# Photon_Pixel_Shield_v7_no_diode_no_fuse.net
KiCad netlist of a schematic drawn in EAGLE
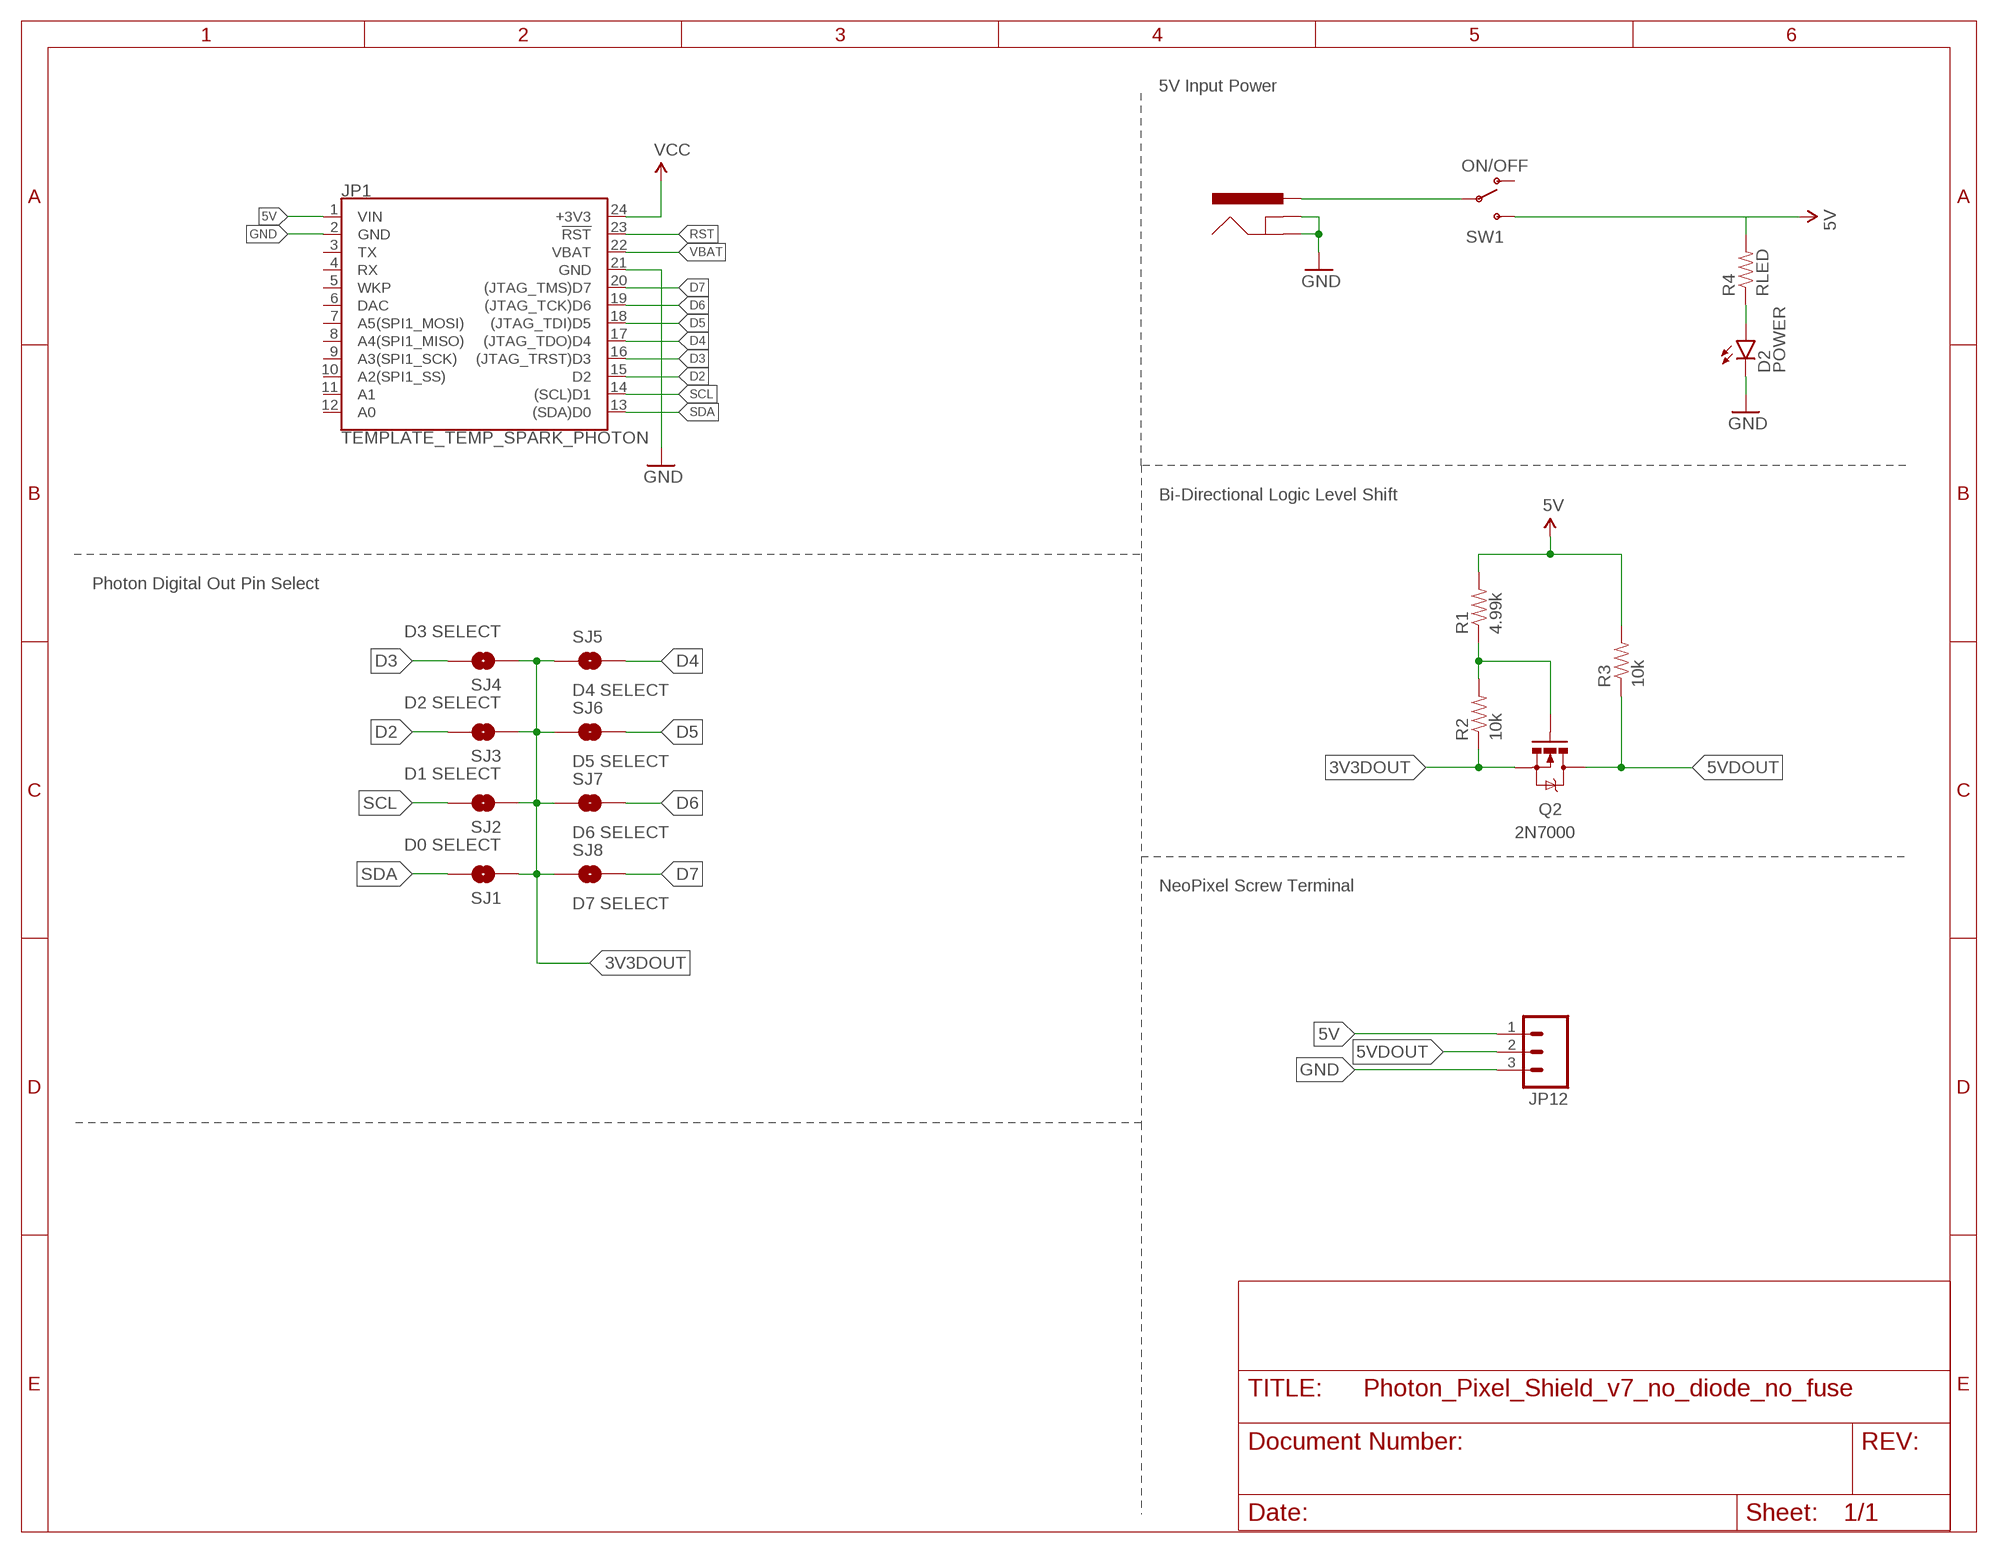
[diagram p0: schematic, sheet 1]

(export (version "E")
  (design (tool "Eeschema 10.0.6"))
  (components
    (comp (ref "D2")
      (value "POWER")
      (footprint "eagle-import:LED3MM")
      (libsource (lib "eagle-import") (part "LED3MM"))
    )
    (comp (ref "J1")
      (value "POWER_JACKPTH")
      (footprint "eagle-import:POWER_JACK_PTH")
      (libsource (lib "eagle-import") (part "POWER_JACKPTH"))
    )
    (comp (ref "JP1")
      (value "TEMPLATE_TEMP_SPARK_PHOTON")
      (footprint "eagle-import:TEMPLATE_TEMP_SPARK_PHOTON")
      (libsource (lib "eagle-import") (part "TEMPLATE_TEMP_SPARK_PHOTON"))
    )
    (comp (ref "JP12")
      (value "M03SCREW")
      (footprint "eagle-import:SCREWTERMINAL-3.5MM-3")
      (libsource (lib "eagle-import") (part "M03SCREW"))
    )
    (comp (ref "Q2")
      (value "2N7000")
      (footprint "eagle-import:TO-92")
      (libsource (lib "eagle-import") (part "MOSFET-NCHANNEL2N7000"))
    )
    (comp (ref "R1")
      (value "4.99k")
      (footprint "eagle-import:AXIAL-0.3")
      (libsource (lib "eagle-import") (part "10KOHM-1/4W-1%(PTH)HORIZ"))
    )
    (comp (ref "R2")
      (value "10k")
      (footprint "eagle-import:AXIAL-0.3")
      (libsource (lib "eagle-import") (part "10KOHM-1/4W-1%(PTH)HORIZ"))
    )
    (comp (ref "R3")
      (value "10k")
      (footprint "eagle-import:AXIAL-0.3")
      (libsource (lib "eagle-import") (part "10KOHM-1/4W-1%(PTH)HORIZ"))
    )
    (comp (ref "R4")
      (value "RLED")
      (footprint "eagle-import:AXIAL-0.3")
      (libsource (lib "eagle-import") (part "10KOHM-1/4W-1%(PTH)HORIZ"))
    )
    (comp (ref "SJ1")
      (value "D0 SELECT")
      (footprint "eagle-import:SJ_2S-NO")
      (libsource (lib "eagle-import") (part "SOLDERJUMPERNO"))
    )
    (comp (ref "SJ2")
      (value "D1 SELECT")
      (footprint "eagle-import:SJ_2S-NO")
      (libsource (lib "eagle-import") (part "SOLDERJUMPERNO"))
    )
    (comp (ref "SJ3")
      (value "D2 SELECT")
      (footprint "eagle-import:SJ_2S-NO")
      (libsource (lib "eagle-import") (part "SOLDERJUMPERNO"))
    )
    (comp (ref "SJ4")
      (value "D3 SELECT")
      (footprint "eagle-import:SJ_2S-NO")
      (libsource (lib "eagle-import") (part "SOLDERJUMPERNO"))
    )
    (comp (ref "SJ5")
      (value "D4 SELECT")
      (footprint "eagle-import:SJ_2S-NO")
      (libsource (lib "eagle-import") (part "SOLDERJUMPERNO"))
    )
    (comp (ref "SJ6")
      (value "D5 SELECT")
      (footprint "eagle-import:SJ_2S-NO")
      (libsource (lib "eagle-import") (part "SOLDERJUMPERNO"))
    )
    (comp (ref "SJ7")
      (value "D6 SELECT")
      (footprint "eagle-import:SJ_2S-NO")
      (libsource (lib "eagle-import") (part "SOLDERJUMPERNO"))
    )
    (comp (ref "SJ8")
      (value "D7 SELECT")
      (footprint "eagle-import:SJ_2S-NO")
      (libsource (lib "eagle-import") (part "SOLDERJUMPERNO"))
    )
    (comp (ref "SW1")
      (value "ON/OFF")
      (footprint "eagle-import:SWITCH-SPST")
      (libsource (lib "eagle-import") (part "SWITCH-SPSTPTH"))
    )
  )
  (nets
    (net (code "1") (name "3V3DOUT") (class "Default")
      (node (ref "Q2") (pin "1") (pinfunction "S_1") (pintype "passive"))
      (node (ref "R2") (pin "P$1") (pinfunction "1_P$1") (pintype "passive"))
      (node (ref "SJ1") (pin "1") (pinfunction "1_1") (pintype "passive"))
      (node (ref "SJ2") (pin "1") (pinfunction "1_1") (pintype "passive"))
      (node (ref "SJ3") (pin "1") (pinfunction "1_1") (pintype "passive"))
      (node (ref "SJ4") (pin "1") (pinfunction "1_1") (pintype "passive"))
      (node (ref "SJ5") (pin "1") (pinfunction "1_1") (pintype "passive"))
      (node (ref "SJ6") (pin "1") (pinfunction "1_1") (pintype "passive"))
      (node (ref "SJ7") (pin "1") (pinfunction "1_1") (pintype "passive"))
      (node (ref "SJ8") (pin "1") (pinfunction "1_1") (pintype "passive"))
    )
    (net (code "2") (name "5V") (class "Default")
      (node (ref "JP1") (pin "1") (pinfunction "VIN_1") (pintype "bidirectional"))
      (node (ref "JP12") (pin "1") (pinfunction "1_1") (pintype "passive"))
      (node (ref "R1") (pin "P$2") (pinfunction "2_P$2") (pintype "passive"))
      (node (ref "R3") (pin "P$2") (pinfunction "2_P$2") (pintype "passive"))
      (node (ref "R4") (pin "P$2") (pinfunction "2_P$2") (pintype "passive"))
      (node (ref "SW1") (pin "3") (pinfunction "S_3") (pintype "passive"))
    )
    (net (code "3") (name "5VDOUT") (class "Default")
      (node (ref "JP12") (pin "2") (pinfunction "2_2") (pintype "passive"))
      (node (ref "Q2") (pin "3") (pinfunction "D_3") (pintype "passive"))
      (node (ref "R3") (pin "P$1") (pinfunction "1_P$1") (pintype "passive"))
    )
    (net (code "4") (name "D2") (class "Default")
      (node (ref "JP1") (pin "15") (pinfunction "D2_15") (pintype "bidirectional"))
      (node (ref "SJ3") (pin "2") (pinfunction "2_2") (pintype "passive"))
    )
    (net (code "5") (name "D3") (class "Default")
      (node (ref "JP1") (pin "16") (pinfunction "(JTAG_TRST)D3_16") (pintype "bidirectional"))
      (node (ref "SJ4") (pin "2") (pinfunction "2_2") (pintype "passive"))
    )
    (net (code "6") (name "D4") (class "Default")
      (node (ref "JP1") (pin "17") (pinfunction "(JTAG_TDO)D4_17") (pintype "bidirectional"))
      (node (ref "SJ5") (pin "2") (pinfunction "2_2") (pintype "passive"))
    )
    (net (code "7") (name "D5") (class "Default")
      (node (ref "JP1") (pin "18") (pinfunction "(JTAG_TDI)D5_18") (pintype "bidirectional"))
      (node (ref "SJ6") (pin "2") (pinfunction "2_2") (pintype "passive"))
    )
    (net (code "8") (name "D6") (class "Default")
      (node (ref "JP1") (pin "19") (pinfunction "(JTAG_TCK)D6_19") (pintype "bidirectional"))
      (node (ref "SJ7") (pin "2") (pinfunction "2_2") (pintype "passive"))
    )
    (net (code "9") (name "D7") (class "Default")
      (node (ref "JP1") (pin "20") (pinfunction "(JTAG_TMS)D7_20") (pintype "bidirectional"))
      (node (ref "SJ8") (pin "2") (pinfunction "2_2") (pintype "passive"))
    )
    (net (code "10") (name "GND") (class "Default")
      (node (ref "D2") (pin "K") (pinfunction "C_K") (pintype "passive"))
      (node (ref "J1") (pin "GND") (pinfunction "GND_GND") (pintype "bidirectional"))
      (node (ref "J1") (pin "GNDBREAK") (pinfunction "GNDBREAK_GNDBREAK") (pintype "bidirectional"))
      (node (ref "JP1") (pin "2") (pinfunction "GND_2") (pintype "bidirectional"))
      (node (ref "JP1") (pin "21") (pinfunction "GND_21") (pintype "bidirectional"))
      (node (ref "JP12") (pin "3") (pinfunction "3_3") (pintype "passive"))
    )
    (net (code "11") (name "Net-(Q2-G)") (class "Default")
      (node (ref "Q2") (pin "2") (pinfunction "G_2") (pintype "passive"))
      (node (ref "R1") (pin "P$1") (pinfunction "1_P$1") (pintype "passive"))
      (node (ref "R2") (pin "P$2") (pinfunction "2_P$2") (pintype "passive"))
    )
    (net (code "12") (name "Net-(R4-1)") (class "Default")
      (node (ref "D2") (pin "A") (pinfunction "A_A") (pintype "passive"))
      (node (ref "R4") (pin "P$1") (pinfunction "1_P$1") (pintype "passive"))
    )
    (net (code "13") (name "Net-(SW1-P)") (class "Default")
      (node (ref "J1") (pin "PWR") (pinfunction "PWR_PWR") (pintype "bidirectional"))
      (node (ref "SW1") (pin "2") (pinfunction "P_2") (pintype "passive"))
    )
    (net (code "14") (name "RST") (class "Default")
      (node (ref "JP1") (pin "23") (pinfunction "~{RST}_23") (pintype "bidirectional"))
    )
    (net (code "15") (name "SCL") (class "Default")
      (node (ref "JP1") (pin "14") (pinfunction "(SCL)D1_14") (pintype "bidirectional"))
      (node (ref "SJ2") (pin "2") (pinfunction "2_2") (pintype "passive"))
    )
    (net (code "16") (name "SDA") (class "Default")
      (node (ref "JP1") (pin "13") (pinfunction "(SDA)D0_13") (pintype "bidirectional"))
      (node (ref "SJ1") (pin "2") (pinfunction "2_2") (pintype "passive"))
    )
    (net (code "17") (name "VBAT") (class "Default")
      (node (ref "JP1") (pin "22") (pinfunction "VBAT_22") (pintype "bidirectional"))
    )
    (net (code "18") (name "VCC") (class "Default")
      (node (ref "JP1") (pin "24") (pinfunction "+3V3_24") (pintype "bidirectional"))
    )
    (net (code "19") (name "unconnected-(JP1-A0-Pad12)") (class "Default")
      (node (ref "JP1") (pin "12") (pinfunction "A0_12") (pintype "bidirectional"))
    )
    (net (code "20") (name "unconnected-(JP1-A1-Pad11)") (class "Default")
      (node (ref "JP1") (pin "11") (pinfunction "A1_11") (pintype "bidirectional"))
    )
    (net (code "21") (name "unconnected-(JP1-A2(SPI1_SS)-Pad10)") (class "Default")
      (node (ref "JP1") (pin "10") (pinfunction "A2(SPI1_SS)_10") (pintype "bidirectional"))
    )
    (net (code "22") (name "unconnected-(JP1-A3(SPI1_SCK)-Pad9)") (class "Default")
      (node (ref "JP1") (pin "9") (pinfunction "A3(SPI1_SCK)_9") (pintype "bidirectional"))
    )
    (net (code "23") (name "unconnected-(JP1-A4(SPI1_MISO)-Pad8)") (class "Default")
      (node (ref "JP1") (pin "8") (pinfunction "A4(SPI1_MISO)_8") (pintype "bidirectional"))
    )
    (net (code "24") (name "unconnected-(JP1-A5(SPI1_MOSI)-Pad7)") (class "Default")
      (node (ref "JP1") (pin "7") (pinfunction "A5(SPI1_MOSI)_7") (pintype "bidirectional"))
    )
    (net (code "25") (name "unconnected-(JP1-DAC-Pad6)") (class "Default")
      (node (ref "JP1") (pin "6") (pinfunction "DAC_6") (pintype "bidirectional"))
    )
    (net (code "26") (name "unconnected-(JP1-RX-Pad4)") (class "Default")
      (node (ref "JP1") (pin "4") (pinfunction "RX_4") (pintype "bidirectional"))
    )
    (net (code "27") (name "unconnected-(JP1-TX-Pad3)") (class "Default")
      (node (ref "JP1") (pin "3") (pinfunction "TX_3") (pintype "bidirectional"))
    )
    (net (code "28") (name "unconnected-(JP1-WKP-Pad5)") (class "Default")
      (node (ref "JP1") (pin "5") (pinfunction "WKP_5") (pintype "bidirectional"))
    )
    (net (code "29") (name "unconnected-(SW1-O-Pad1)") (class "Default")
      (node (ref "SW1") (pin "1") (pinfunction "O_1") (pintype "passive"))
    )
  )
)
